# dianlutu.net
KiCad netlist of a schematic drawn in EAGLE
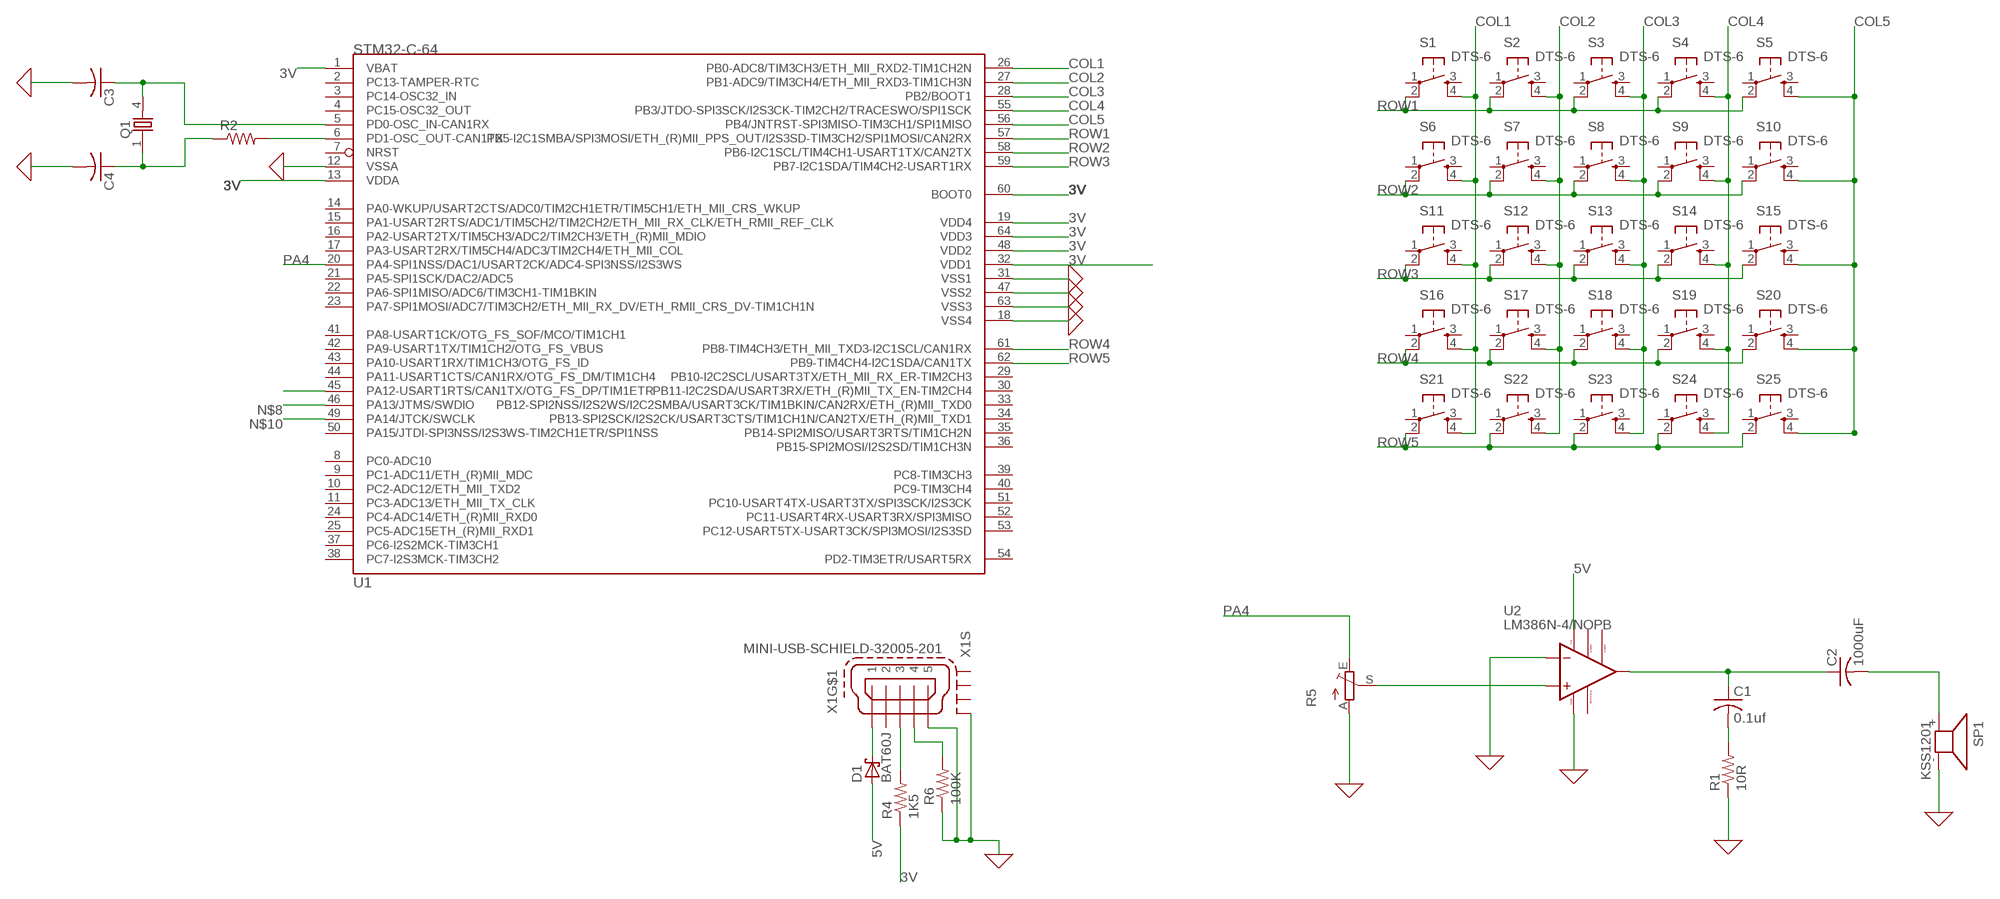
[diagram p0: schematic, sheet 1]

(export (version "E")
  (design (tool "Eeschema 10.0.6"))
  (components
    (comp (ref "C1")
      (value "0.1uf")
      (footprint "eagle-import:C0805")
      (libsource (lib "eagle-import") (part "C-USC0805"))
    )
    (comp (ref "C2")
      (value "1000uF")
      (footprint "eagle-import:C0805")
      (libsource (lib "eagle-import") (part "C-USC0805"))
    )
    (comp (ref "C3")
      (value "C-USC0805")
      (footprint "eagle-import:C0805")
      (libsource (lib "eagle-import") (part "C-USC0805"))
    )
    (comp (ref "C4")
      (value "C-USC0805")
      (footprint "eagle-import:C0805")
      (libsource (lib "eagle-import") (part "C-USC0805"))
    )
    (comp (ref "D1")
      (value "BAT60J")
      (footprint "eagle-import:SOD323_ST")
      (libsource (lib "eagle-import") (part "BAT60J"))
    )
    (comp (ref "Q1")
      (value "86SMX")
      (footprint "eagle-import:86SMX")
      (fields (field (name "MF") "C-MAC  FREQUENCY PRODUCTS LTD") (field (name "MPN") "XTAL003321- 86SMX"))
      (libsource (lib "eagle-import") (part "86SMX"))
    )
    (comp (ref "R1")
      (value "10R")
      (footprint "eagle-import:R0805")
      (libsource (lib "eagle-import") (part "R-US_R0805"))
    )
    (comp (ref "R2")
      (value "R-US_R0805")
      (footprint "eagle-import:R0805")
      (libsource (lib "eagle-import") (part "R-US_R0805"))
    )
    (comp (ref "R4")
      (value "1K5")
      (footprint "eagle-import:R0805")
      (libsource (lib "eagle-import") (part "resistor_348_R-US_R0805"))
    )
    (comp (ref "R5")
      (value "TRIM_EU-S63S")
      (footprint "eagle-import:S63S")
      (libsource (lib "eagle-import") (part "TRIM_EU-S63S"))
    )
    (comp (ref "R6")
      (value "100K")
      (footprint "eagle-import:M0805")
      (libsource (lib "eagle-import") (part "resistor_348_R-US_M0805"))
    )
    (comp (ref "S1")
      (value "DTS-6")
      (footprint "eagle-import:DTS-6")
      (libsource (lib "eagle-import") (part "DTS-6"))
    )
    (comp (ref "S2")
      (value "DTS-6")
      (footprint "eagle-import:DTS-6")
      (libsource (lib "eagle-import") (part "DTS-6"))
    )
    (comp (ref "S3")
      (value "DTS-6")
      (footprint "eagle-import:DTS-6")
      (libsource (lib "eagle-import") (part "DTS-6"))
    )
    (comp (ref "S4")
      (value "DTS-6")
      (footprint "eagle-import:DTS-6")
      (libsource (lib "eagle-import") (part "DTS-6"))
    )
    (comp (ref "S5")
      (value "DTS-6")
      (footprint "eagle-import:DTS-6")
      (libsource (lib "eagle-import") (part "DTS-6"))
    )
    (comp (ref "S6")
      (value "DTS-6")
      (footprint "eagle-import:DTS-6")
      (libsource (lib "eagle-import") (part "DTS-6"))
    )
    (comp (ref "S7")
      (value "DTS-6")
      (footprint "eagle-import:DTS-6")
      (libsource (lib "eagle-import") (part "DTS-6"))
    )
    (comp (ref "S8")
      (value "DTS-6")
      (footprint "eagle-import:DTS-6")
      (libsource (lib "eagle-import") (part "DTS-6"))
    )
    (comp (ref "S9")
      (value "DTS-6")
      (footprint "eagle-import:DTS-6")
      (libsource (lib "eagle-import") (part "DTS-6"))
    )
    (comp (ref "S10")
      (value "DTS-6")
      (footprint "eagle-import:DTS-6")
      (libsource (lib "eagle-import") (part "DTS-6"))
    )
    (comp (ref "S11")
      (value "DTS-6")
      (footprint "eagle-import:DTS-6")
      (libsource (lib "eagle-import") (part "DTS-6"))
    )
    (comp (ref "S12")
      (value "DTS-6")
      (footprint "eagle-import:DTS-6")
      (libsource (lib "eagle-import") (part "DTS-6"))
    )
    (comp (ref "S13")
      (value "DTS-6")
      (footprint "eagle-import:DTS-6")
      (libsource (lib "eagle-import") (part "DTS-6"))
    )
    (comp (ref "S14")
      (value "DTS-6")
      (footprint "eagle-import:DTS-6")
      (libsource (lib "eagle-import") (part "DTS-6"))
    )
    (comp (ref "S15")
      (value "DTS-6")
      (footprint "eagle-import:DTS-6")
      (libsource (lib "eagle-import") (part "DTS-6"))
    )
    (comp (ref "S16")
      (value "DTS-6")
      (footprint "eagle-import:DTS-6")
      (libsource (lib "eagle-import") (part "DTS-6"))
    )
    (comp (ref "S17")
      (value "DTS-6")
      (footprint "eagle-import:DTS-6")
      (libsource (lib "eagle-import") (part "DTS-6"))
    )
    (comp (ref "S18")
      (value "DTS-6")
      (footprint "eagle-import:DTS-6")
      (libsource (lib "eagle-import") (part "DTS-6"))
    )
    (comp (ref "S19")
      (value "DTS-6")
      (footprint "eagle-import:DTS-6")
      (libsource (lib "eagle-import") (part "DTS-6"))
    )
    (comp (ref "S20")
      (value "DTS-6")
      (footprint "eagle-import:DTS-6")
      (libsource (lib "eagle-import") (part "DTS-6"))
    )
    (comp (ref "S21")
      (value "DTS-6")
      (footprint "eagle-import:DTS-6")
      (libsource (lib "eagle-import") (part "DTS-6"))
    )
    (comp (ref "S22")
      (value "DTS-6")
      (footprint "eagle-import:DTS-6")
      (libsource (lib "eagle-import") (part "DTS-6"))
    )
    (comp (ref "S23")
      (value "DTS-6")
      (footprint "eagle-import:DTS-6")
      (libsource (lib "eagle-import") (part "DTS-6"))
    )
    (comp (ref "S24")
      (value "DTS-6")
      (footprint "eagle-import:DTS-6")
      (libsource (lib "eagle-import") (part "DTS-6"))
    )
    (comp (ref "S25")
      (value "DTS-6")
      (footprint "eagle-import:DTS-6")
      (libsource (lib "eagle-import") (part "DTS-6"))
    )
    (comp (ref "SP1")
      (value "KSS1201")
      (footprint "eagle-import:KSS1201")
      (libsource (lib "eagle-import") (part "KSS1201"))
    )
    (comp (ref "U1")
      (value "STM32-C-64")
      (footprint "eagle-import:LQFP64")
      (libsource (lib "eagle-import") (part "STM32-C-64"))
    )
    (comp (ref "U2")
      (value "LM386N-4/NOPB")
      (footprint "eagle-import:DIP794W45P254L1016H508Q8")
      (fields (field (name "MF") "Texas Instruments"))
      (libsource (lib "eagle-import") (part "LM386N-4/NOPB"))
    )
    (comp (ref "X1")
      (value "MINI-USB-SCHIELD-32005-201")
      (footprint "eagle-import:32005-201")
      (libsource (lib "eagle-import") (part "MINI-USB-SCHIELD-32005-201"))
    )
  )
  (nets
    (net (code "1") (name "/3V") (class "Default")
      (node (ref "R4") (pin "1") (pinfunction "1_1") (pintype "passive"))
      (node (ref "U1") (pin "1") (pinfunction "VBAT_1") (pintype "power_in"))
      (node (ref "U1") (pin "13") (pinfunction "VDDA_13") (pintype "power_in"))
      (node (ref "U1") (pin "19") (pinfunction "VDD4_19") (pintype "bidirectional"))
      (node (ref "U1") (pin "32") (pinfunction "VDD1_32") (pintype "power_in"))
      (node (ref "U1") (pin "48") (pinfunction "VDD2_48") (pintype "power_in"))
      (node (ref "U1") (pin "60") (pinfunction "BOOT0_60") (pintype "input"))
      (node (ref "U1") (pin "64") (pinfunction "VDD3_64") (pintype "power_in"))
    )
    (net (code "2") (name "/5V") (class "Default")
      (node (ref "D1") (pin "A") (pinfunction "A_A") (pintype "passive"))
      (node (ref "U2") (pin "6") (pinfunction "VS_6") (pintype "power_in"))
    )
    (net (code "3") (name "/COL1") (class "Default")
      (node (ref "S1") (pin "4") (pinfunction "4_4") (pintype "passive"))
      (node (ref "S11") (pin "4") (pinfunction "4_4") (pintype "passive"))
      (node (ref "S16") (pin "4") (pinfunction "4_4") (pintype "passive"))
      (node (ref "S21") (pin "4") (pinfunction "4_4") (pintype "passive"))
      (node (ref "S6") (pin "4") (pinfunction "4_4") (pintype "passive"))
      (node (ref "U1") (pin "26") (pinfunction "PB0-ADC8/TIM3CH3/ETH_MII_RXD2-TIM1CH2N_26") (pintype "bidirectional"))
    )
    (net (code "4") (name "/COL2") (class "Default")
      (node (ref "S12") (pin "4") (pinfunction "4_4") (pintype "passive"))
      (node (ref "S17") (pin "4") (pinfunction "4_4") (pintype "passive"))
      (node (ref "S2") (pin "4") (pinfunction "4_4") (pintype "passive"))
      (node (ref "S22") (pin "4") (pinfunction "4_4") (pintype "passive"))
      (node (ref "S7") (pin "4") (pinfunction "4_4") (pintype "passive"))
      (node (ref "U1") (pin "27") (pinfunction "PB1-ADC9/TIM3CH4/ETH_MII_RXD3-TIM1CH3N_27") (pintype "bidirectional"))
    )
    (net (code "5") (name "/COL3") (class "Default")
      (node (ref "S13") (pin "4") (pinfunction "4_4") (pintype "passive"))
      (node (ref "S18") (pin "4") (pinfunction "4_4") (pintype "passive"))
      (node (ref "S23") (pin "4") (pinfunction "4_4") (pintype "passive"))
      (node (ref "S3") (pin "4") (pinfunction "4_4") (pintype "passive"))
      (node (ref "S8") (pin "4") (pinfunction "4_4") (pintype "passive"))
      (node (ref "U1") (pin "28") (pinfunction "PB2/BOOT1_28") (pintype "bidirectional"))
    )
    (net (code "6") (name "/COL4") (class "Default")
      (node (ref "S14") (pin "4") (pinfunction "4_4") (pintype "passive"))
      (node (ref "S19") (pin "4") (pinfunction "4_4") (pintype "passive"))
      (node (ref "S24") (pin "4") (pinfunction "4_4") (pintype "passive"))
      (node (ref "S4") (pin "4") (pinfunction "4_4") (pintype "passive"))
      (node (ref "S9") (pin "4") (pinfunction "4_4") (pintype "passive"))
      (node (ref "U1") (pin "55") (pinfunction "PB3/JTDO-SPI3SCK/I2S3CK-TIM2CH2/TRACESWO/SPI1SCK_55") (pintype "bidirectional"))
    )
    (net (code "7") (name "/COL5") (class "Default")
      (node (ref "S10") (pin "4") (pinfunction "4_4") (pintype "passive"))
      (node (ref "S15") (pin "4") (pinfunction "4_4") (pintype "passive"))
      (node (ref "S20") (pin "4") (pinfunction "4_4") (pintype "passive"))
      (node (ref "S25") (pin "4") (pinfunction "4_4") (pintype "passive"))
      (node (ref "S5") (pin "4") (pinfunction "4_4") (pintype "passive"))
      (node (ref "U1") (pin "56") (pinfunction "PB4/JNTRST-SPI3MISO-TIM3CH1/SPI1MISO_56") (pintype "bidirectional"))
    )
    (net (code "8") (name "/N$8") (class "Default")
      (node (ref "U1") (pin "46") (pinfunction "PA13/JTMS/SWDIO_46") (pintype "bidirectional"))
    )
    (net (code "9") (name "/N$10") (class "Default")
      (node (ref "U1") (pin "49") (pinfunction "PA14/JTCK/SWCLK_49") (pintype "bidirectional"))
    )
    (net (code "10") (name "/PA4") (class "Default")
      (node (ref "R5") (pin "E") (pinfunction "E_E") (pintype "passive"))
      (node (ref "U1") (pin "20") (pinfunction "PA4-SPI1NSS/DAC1/USART2CK/ADC4-SPI3NSS/I2S3WS_20") (pintype "bidirectional"))
    )
    (net (code "11") (name "/ROW1") (class "Default")
      (node (ref "S1") (pin "2") (pinfunction "2_2") (pintype "passive"))
      (node (ref "S2") (pin "2") (pinfunction "2_2") (pintype "passive"))
      (node (ref "S3") (pin "2") (pinfunction "2_2") (pintype "passive"))
      (node (ref "S4") (pin "2") (pinfunction "2_2") (pintype "passive"))
      (node (ref "S5") (pin "2") (pinfunction "2_2") (pintype "passive"))
      (node (ref "U1") (pin "57") (pinfunction "PB5-I2C1SMBA/SPI3MOSI/ETH_(R)MII_PPS_OUT/I2S3SD-TIM3CH2/SPI1MOSI/CAN2RX_57") (pintype "bidirectional"))
    )
    (net (code "12") (name "/ROW2") (class "Default")
      (node (ref "S10") (pin "2") (pinfunction "2_2") (pintype "passive"))
      (node (ref "S6") (pin "2") (pinfunction "2_2") (pintype "passive"))
      (node (ref "S7") (pin "2") (pinfunction "2_2") (pintype "passive"))
      (node (ref "S8") (pin "2") (pinfunction "2_2") (pintype "passive"))
      (node (ref "S9") (pin "2") (pinfunction "2_2") (pintype "passive"))
      (node (ref "U1") (pin "58") (pinfunction "PB6-I2C1SCL/TIM4CH1-USART1TX/CAN2TX_58") (pintype "bidirectional"))
    )
    (net (code "13") (name "/ROW3") (class "Default")
      (node (ref "S11") (pin "2") (pinfunction "2_2") (pintype "passive"))
      (node (ref "S12") (pin "2") (pinfunction "2_2") (pintype "passive"))
      (node (ref "S13") (pin "2") (pinfunction "2_2") (pintype "passive"))
      (node (ref "S14") (pin "2") (pinfunction "2_2") (pintype "passive"))
      (node (ref "S15") (pin "2") (pinfunction "2_2") (pintype "passive"))
      (node (ref "U1") (pin "59") (pinfunction "PB7-I2C1SDA/TIM4CH2-USART1RX_59") (pintype "bidirectional"))
    )
    (net (code "14") (name "/ROW4") (class "Default")
      (node (ref "S16") (pin "2") (pinfunction "2_2") (pintype "passive"))
      (node (ref "S17") (pin "2") (pinfunction "2_2") (pintype "passive"))
      (node (ref "S18") (pin "2") (pinfunction "2_2") (pintype "passive"))
      (node (ref "S19") (pin "2") (pinfunction "2_2") (pintype "passive"))
      (node (ref "S20") (pin "2") (pinfunction "2_2") (pintype "passive"))
      (node (ref "U1") (pin "61") (pinfunction "PB8-TIM4CH3/ETH_MII_TXD3-I2C1SCL/CAN1RX_61") (pintype "bidirectional"))
    )
    (net (code "15") (name "/ROW5") (class "Default")
      (node (ref "S21") (pin "2") (pinfunction "2_2") (pintype "passive"))
      (node (ref "S22") (pin "2") (pinfunction "2_2") (pintype "passive"))
      (node (ref "S23") (pin "2") (pinfunction "2_2") (pintype "passive"))
      (node (ref "S24") (pin "2") (pinfunction "2_2") (pintype "passive"))
      (node (ref "S25") (pin "2") (pinfunction "2_2") (pintype "passive"))
      (node (ref "U1") (pin "62") (pinfunction "PB9-TIM4CH4-I2C1SDA/CAN1TX_62") (pintype "bidirectional"))
    )
    (net (code "16") (name "GND") (class "Default")
      (node (ref "C3") (pin "2") (pinfunction "2_2") (pintype "passive"))
      (node (ref "C4") (pin "2") (pinfunction "2_2") (pintype "passive"))
      (node (ref "R1") (pin "1") (pinfunction "1_1") (pintype "passive"))
      (node (ref "R5") (pin "A") (pinfunction "A_A") (pintype "passive"))
      (node (ref "R6") (pin "1") (pinfunction "1_1") (pintype "passive"))
      (node (ref "SP1") (pin "-") (pinfunction "2_-") (pintype "passive"))
      (node (ref "U1") (pin "12") (pinfunction "VSSA_12") (pintype "power_in"))
      (node (ref "U1") (pin "18") (pinfunction "VSS4_18") (pintype "bidirectional"))
      (node (ref "U1") (pin "31") (pinfunction "VSS1_31") (pintype "power_in"))
      (node (ref "U1") (pin "47") (pinfunction "VSS2_47") (pintype "power_in"))
      (node (ref "U1") (pin "63") (pinfunction "VSS3_63") (pintype "power_in"))
      (node (ref "U2") (pin "2") (pinfunction "-INPUT_2") (pintype "input"))
      (node (ref "U2") (pin "4") (pinfunction "GND_4") (pintype "power_in"))
      (node (ref "X1") (pin "5") (pinfunction "5_5") (pintype "passive"))
      (node (ref "X1") (pin "M1") (pinfunction "S1_M1") (pintype "passive"))
    )
    (net (code "17") (name "Net-(C1-Pad2)") (class "Default")
      (node (ref "C1") (pin "2") (pinfunction "2_2") (pintype "passive"))
      (node (ref "R1") (pin "2") (pinfunction "2_2") (pintype "passive"))
    )
    (net (code "18") (name "Net-(C4-Pad1)") (class "Default")
      (node (ref "C4") (pin "1") (pinfunction "1_1") (pintype "passive"))
      (node (ref "Q1") (pin "1") (pinfunction "1_1") (pintype "passive"))
      (node (ref "R2") (pin "1") (pinfunction "1_1") (pintype "passive"))
    )
    (net (code "19") (name "Net-(D1-PadC)") (class "Default")
      (node (ref "D1") (pin "C") (pinfunction "C_C") (pintype "passive"))
      (node (ref "X1") (pin "1") (pinfunction "1_1") (pintype "passive"))
    )
    (net (code "20") (name "Net-(Q1-2)") (class "Default")
      (node (ref "C3") (pin "1") (pinfunction "1_1") (pintype "passive"))
      (node (ref "Q1") (pin "4") (pinfunction "2_4") (pintype "passive"))
      (node (ref "U1") (pin "5") (pinfunction "PD0-OSC_IN-CAN1RX_5") (pintype "input"))
    )
    (net (code "21") (name "Net-(R4-Pad2)") (class "Default")
      (node (ref "R4") (pin "2") (pinfunction "2_2") (pintype "passive"))
      (node (ref "X1") (pin "3") (pinfunction "3_3") (pintype "passive"))
    )
    (net (code "22") (name "Net-(R6-Pad2)") (class "Default")
      (node (ref "R6") (pin "2") (pinfunction "2_2") (pintype "passive"))
      (node (ref "X1") (pin "4") (pinfunction "4_4") (pintype "passive"))
    )
    (net (code "23") (name "Net-(SP1-1)") (class "Default")
      (node (ref "C2") (pin "2") (pinfunction "2_2") (pintype "passive"))
      (node (ref "SP1") (pin "+") (pinfunction "1_+") (pintype "passive"))
    )
    (net (code "24") (name "Net-(U1-PD1-OSC_OUT-CAN1TX)") (class "Default")
      (node (ref "R2") (pin "2") (pinfunction "2_2") (pintype "passive"))
      (node (ref "U1") (pin "6") (pinfunction "PD1-OSC_OUT-CAN1TX_6") (pintype "output"))
    )
    (net (code "25") (name "Net-(U2-+INPUT)") (class "Default")
      (node (ref "R5") (pin "S") (pinfunction "S_S") (pintype "passive"))
      (node (ref "U2") (pin "3") (pinfunction "+INPUT_3") (pintype "input"))
    )
    (net (code "26") (name "Net-(U2-VOUT)") (class "Default")
      (node (ref "C1") (pin "1") (pinfunction "1_1") (pintype "passive"))
      (node (ref "C2") (pin "1") (pinfunction "1_1") (pintype "passive"))
      (node (ref "U2") (pin "5") (pinfunction "VOUT_5") (pintype "output"))
    )
    (net (code "27") (name "unconnected-(S1-Pad1)") (class "Default")
      (node (ref "S1") (pin "1") (pinfunction "1_1") (pintype "passive"))
    )
    (net (code "28") (name "unconnected-(S1-Pad3)") (class "Default")
      (node (ref "S1") (pin "3") (pinfunction "3_3") (pintype "passive"))
    )
    (net (code "29") (name "unconnected-(S2-Pad1)") (class "Default")
      (node (ref "S2") (pin "1") (pinfunction "1_1") (pintype "passive"))
    )
    (net (code "30") (name "unconnected-(S2-Pad3)") (class "Default")
      (node (ref "S2") (pin "3") (pinfunction "3_3") (pintype "passive"))
    )
    (net (code "31") (name "unconnected-(S3-Pad1)") (class "Default")
      (node (ref "S3") (pin "1") (pinfunction "1_1") (pintype "passive"))
    )
    (net (code "32") (name "unconnected-(S3-Pad3)") (class "Default")
      (node (ref "S3") (pin "3") (pinfunction "3_3") (pintype "passive"))
    )
    (net (code "33") (name "unconnected-(S4-Pad1)") (class "Default")
      (node (ref "S4") (pin "1") (pinfunction "1_1") (pintype "passive"))
    )
    (net (code "34") (name "unconnected-(S4-Pad3)") (class "Default")
      (node (ref "S4") (pin "3") (pinfunction "3_3") (pintype "passive"))
    )
    (net (code "35") (name "unconnected-(S5-Pad1)") (class "Default")
      (node (ref "S5") (pin "1") (pinfunction "1_1") (pintype "passive"))
    )
    (net (code "36") (name "unconnected-(S5-Pad3)") (class "Default")
      (node (ref "S5") (pin "3") (pinfunction "3_3") (pintype "passive"))
    )
    (net (code "37") (name "unconnected-(S6-Pad1)") (class "Default")
      (node (ref "S6") (pin "1") (pinfunction "1_1") (pintype "passive"))
    )
    (net (code "38") (name "unconnected-(S6-Pad3)") (class "Default")
      (node (ref "S6") (pin "3") (pinfunction "3_3") (pintype "passive"))
    )
    (net (code "39") (name "unconnected-(S7-Pad1)") (class "Default")
      (node (ref "S7") (pin "1") (pinfunction "1_1") (pintype "passive"))
    )
    (net (code "40") (name "unconnected-(S7-Pad3)") (class "Default")
      (node (ref "S7") (pin "3") (pinfunction "3_3") (pintype "passive"))
    )
    (net (code "41") (name "unconnected-(S8-Pad1)") (class "Default")
      (node (ref "S8") (pin "1") (pinfunction "1_1") (pintype "passive"))
    )
    (net (code "42") (name "unconnected-(S8-Pad3)") (class "Default")
      (node (ref "S8") (pin "3") (pinfunction "3_3") (pintype "passive"))
    )
    (net (code "43") (name "unconnected-(S9-Pad1)") (class "Default")
      (node (ref "S9") (pin "1") (pinfunction "1_1") (pintype "passive"))
    )
    (net (code "44") (name "unconnected-(S9-Pad3)") (class "Default")
      (node (ref "S9") (pin "3") (pinfunction "3_3") (pintype "passive"))
    )
    (net (code "45") (name "unconnected-(S10-Pad1)") (class "Default")
      (node (ref "S10") (pin "1") (pinfunction "1_1") (pintype "passive"))
    )
    (net (code "46") (name "unconnected-(S10-Pad3)") (class "Default")
      (node (ref "S10") (pin "3") (pinfunction "3_3") (pintype "passive"))
    )
    (net (code "47") (name "unconnected-(S11-Pad1)") (class "Default")
      (node (ref "S11") (pin "1") (pinfunction "1_1") (pintype "passive"))
    )
    (net (code "48") (name "unconnected-(S11-Pad3)") (class "Default")
      (node (ref "S11") (pin "3") (pinfunction "3_3") (pintype "passive"))
    )
    (net (code "49") (name "unconnected-(S12-Pad1)") (class "Default")
      (node (ref "S12") (pin "1") (pinfunction "1_1") (pintype "passive"))
    )
    (net (code "50") (name "unconnected-(S12-Pad3)") (class "Default")
      (node (ref "S12") (pin "3") (pinfunction "3_3") (pintype "passive"))
    )
    (net (code "51") (name "unconnected-(S13-Pad1)") (class "Default")
      (node (ref "S13") (pin "1") (pinfunction "1_1") (pintype "passive"))
    )
    (net (code "52") (name "unconnected-(S13-Pad3)") (class "Default")
      (node (ref "S13") (pin "3") (pinfunction "3_3") (pintype "passive"))
    )
    (net (code "53") (name "unconnected-(S14-Pad1)") (class "Default")
      (node (ref "S14") (pin "1") (pinfunction "1_1") (pintype "passive"))
    )
    (net (code "54") (name "unconnected-(S14-Pad3)") (class "Default")
      (node (ref "S14") (pin "3") (pinfunction "3_3") (pintype "passive"))
    )
    (net (code "55") (name "unconnected-(S15-Pad1)") (class "Default")
      (node (ref "S15") (pin "1") (pinfunction "1_1") (pintype "passive"))
    )
    (net (code "56") (name "unconnected-(S15-Pad3)") (class "Default")
      (node (ref "S15") (pin "3") (pinfunction "3_3") (pintype "passive"))
    )
    (net (code "57") (name "unconnected-(S16-Pad1)") (class "Default")
      (node (ref "S16") (pin "1") (pinfunction "1_1") (pintype "passive"))
    )
    (net (code "58") (name "unconnected-(S16-Pad3)") (class "Default")
      (node (ref "S16") (pin "3") (pinfunction "3_3") (pintype "passive"))
    )
    (net (code "59") (name "unconnected-(S17-Pad1)") (class "Default")
      (node (ref "S17") (pin "1") (pinfunction "1_1") (pintype "passive"))
    )
    (net (code "60") (name "unconnected-(S17-Pad3)") (class "Default")
      (node (ref "S17") (pin "3") (pinfunction "3_3") (pintype "passive"))
    )
    (net (code "61") (name "unconnected-(S18-Pad1)") (class "Default")
      (node (ref "S18") (pin "1") (pinfunction "1_1") (pintype "passive"))
    )
    (net (code "62") (name "unconnected-(S18-Pad3)") (class "Default")
      (node (ref "S18") (pin "3") (pinfunction "3_3") (pintype "passive"))
    )
    (net (code "63") (name "unconnected-(S19-Pad1)") (class "Default")
      (node (ref "S19") (pin "1") (pinfunction "1_1") (pintype "passive"))
    )
    (net (code "64") (name "unconnected-(S19-Pad3)") (class "Default")
      (node (ref "S19") (pin "3") (pinfunction "3_3") (pintype "passive"))
    )
    (net (code "65") (name "unconnected-(S20-Pad1)") (class "Default")
      (node (ref "S20") (pin "1") (pinfunction "1_1") (pintype "passive"))
    )
    (net (code "66") (name "unconnected-(S20-Pad3)") (class "Default")
      (node (ref "S20") (pin "3") (pinfunction "3_3") (pintype "passive"))
    )
    (net (code "67") (name "unconnected-(S21-Pad1)") (class "Default")
      (node (ref "S21") (pin "1") (pinfunction "1_1") (pintype "passive"))
    )
    (net (code "68") (name "unconnected-(S21-Pad3)") (class "Default")
      (node (ref "S21") (pin "3") (pinfunction "3_3") (pintype "passive"))
    )
    (net (code "69") (name "unconnected-(S22-Pad1)") (class "Default")
      (node (ref "S22") (pin "1") (pinfunction "1_1") (pintype "passive"))
    )
    (net (code "70") (name "unconnected-(S22-Pad3)") (class "Default")
      (node (ref "S22") (pin "3") (pinfunction "3_3") (pintype "passive"))
    )
    (net (code "71") (name "unconnected-(S23-Pad1)") (class "Default")
      (node (ref "S23") (pin "1") (pinfunction "1_1") (pintype "passive"))
    )
    (net (code "72") (name "unconnected-(S23-Pad3)") (class "Default")
      (node (ref "S23") (pin "3") (pinfunction "3_3") (pintype "passive"))
    )
    (net (code "73") (name "unconnected-(S24-Pad1)") (class "Default")
      (node (ref "S24") (pin "1") (pinfunction "1_1") (pintype "passive"))
    )
    (net (code "74") (name "unconnected-(S24-Pad3)") (class "Default")
      (node (ref "S24") (pin "3") (pinfunction "3_3") (pintype "passive"))
    )
    (net (code "75") (name "unconnected-(S25-Pad1)") (class "Default")
      (node (ref "S25") (pin "1") (pinfunction "1_1") (pintype "passive"))
    )
    (net (code "76") (name "unconnected-(S25-Pad3)") (class "Default")
      (node (ref "S25") (pin "3") (pinfunction "3_3") (pintype "passive"))
    )
    (net (code "77") (name "unconnected-(U1-NRST-Pad7)") (class "Default")
      (node (ref "U1") (pin "7") (pinfunction "NRST_7") (pintype "bidirectional"))
    )
    (net (code "78") (name "unconnected-(U1-PA0-WKUP{slash}USART2CTS{slash}ADC0{slash}TIM2CH1ETR{slash}TIM5CH1{slash}ETH_MII_CRS_WKUP-Pad14)") (class "Default")
      (node (ref "U1") (pin "14") (pinfunction "PA0-WKUP/USART2CTS/ADC0/TIM2CH1ETR/TIM5CH1/ETH_MII_CRS_WKUP_14") (pintype "bidirectional"))
    )
    (net (code "79") (name "unconnected-(U1-PA1-USART2RTS{slash}ADC1{slash}TIM5CH2{slash}TIM2CH2{slash}ETH_MII_RX_CLK{slash}ETH_RMII_REF_CLK-Pad15)") (class "Default")
      (node (ref "U1") (pin "15") (pinfunction "PA1-USART2RTS/ADC1/TIM5CH2/TIM2CH2/ETH_MII_RX_CLK/ETH_RMII_REF_CLK_15") (pintype "bidirectional"))
    )
    (net (code "80") (name "unconnected-(U1-PA2-USART2TX{slash}TIM5CH3{slash}ADC2{slash}TIM2CH3{slash}ETH_(R)MII_MDIO-Pad16)") (class "Default")
      (node (ref "U1") (pin "16") (pinfunction "PA2-USART2TX/TIM5CH3/ADC2/TIM2CH3/ETH_(R)MII_MDIO_16") (pintype "bidirectional"))
    )
    (net (code "81") (name "unconnected-(U1-PA3-USART2RX{slash}TIM5CH4{slash}ADC3{slash}TIM2CH4{slash}ETH_MII_COL-Pad17)") (class "Default")
      (node (ref "U1") (pin "17") (pinfunction "PA3-USART2RX/TIM5CH4/ADC3/TIM2CH4/ETH_MII_COL_17") (pintype "bidirectional"))
    )
    (net (code "82") (name "unconnected-(U1-PA5-SPI1SCK{slash}DAC2{slash}ADC5-Pad21)") (class "Default")
      (node (ref "U1") (pin "21") (pinfunction "PA5-SPI1SCK/DAC2/ADC5_21") (pintype "bidirectional"))
    )
    (net (code "83") (name "unconnected-(U1-PA6-SPI1MISO{slash}ADC6{slash}TIM3CH1-TIM1BKIN-Pad22)") (class "Default")
      (node (ref "U1") (pin "22") (pinfunction "PA6-SPI1MISO/ADC6/TIM3CH1-TIM1BKIN_22") (pintype "bidirectional"))
    )
    (net (code "84") (name "unconnected-(U1-PA7-SPI1MOSI{slash}ADC7{slash}TIM3CH2{slash}ETH_MII_RX_DV{slash}ETH_RMII_CRS_DV-TIM1CH1N-Pad23)") (class "Default")
      (node (ref "U1") (pin "23") (pinfunction "PA7-SPI1MOSI/ADC7/TIM3CH2/ETH_MII_RX_DV/ETH_RMII_CRS_DV-TIM1CH1N_23") (pintype "bidirectional"))
    )
    (net (code "85") (name "unconnected-(U1-PA8-USART1CK{slash}OTG_FS_SOF{slash}MCO{slash}TIM1CH1-Pad41)") (class "Default")
      (node (ref "U1") (pin "41") (pinfunction "PA8-USART1CK/OTG_FS_SOF/MCO/TIM1CH1_41") (pintype "bidirectional"))
    )
    (net (code "86") (name "unconnected-(U1-PA9-USART1TX{slash}TIM1CH2{slash}OTG_FS_VBUS-Pad42)") (class "Default")
      (node (ref "U1") (pin "42") (pinfunction "PA9-USART1TX/TIM1CH2/OTG_FS_VBUS_42") (pintype "bidirectional"))
    )
    (net (code "87") (name "unconnected-(U1-PA10-USART1RX{slash}TIM1CH3{slash}OTG_FS_ID-Pad43)") (class "Default")
      (node (ref "U1") (pin "43") (pinfunction "PA10-USART1RX/TIM1CH3/OTG_FS_ID_43") (pintype "bidirectional"))
    )
    (net (code "88") (name "unconnected-(U1-PA11-USART1CTS{slash}CAN1RX{slash}OTG_FS_DM{slash}TIM1CH4-Pad44)") (class "Default")
      (node (ref "U1") (pin "44") (pinfunction "PA11-USART1CTS/CAN1RX/OTG_FS_DM/TIM1CH4_44") (pintype "bidirectional"))
    )
    (net (code "89") (name "unconnected-(U1-PA12-USART1RTS{slash}CAN1TX{slash}OTG_FS_DP{slash}TIM1ETR-Pad45)") (class "Default")
      (node (ref "U1") (pin "45") (pinfunction "PA12-USART1RTS/CAN1TX/OTG_FS_DP/TIM1ETR_45") (pintype "bidirectional"))
    )
    (net (code "90") (name "unconnected-(U1-PA15{slash}JTDI-SPI3NSS{slash}I2S3WS-TIM2CH1ETR{slash}SPI1NSS-Pad50)") (class "Default")
      (node (ref "U1") (pin "50") (pinfunction "PA15/JTDI-SPI3NSS/I2S3WS-TIM2CH1ETR/SPI1NSS_50") (pintype "bidirectional"))
    )
    (net (code "91") (name "unconnected-(U1-PB10-I2C2SCL{slash}USART3TX{slash}ETH_MII_RX_ER-TIM2CH3-Pad29)") (class "Default")
      (node (ref "U1") (pin "29") (pinfunction "PB10-I2C2SCL/USART3TX/ETH_MII_RX_ER-TIM2CH3_29") (pintype "bidirectional"))
    )
    (net (code "92") (name "unconnected-(U1-PB11-I2C2SDA{slash}USART3RX{slash}ETH_(R)MII_TX_EN-TIM2CH4-Pad30)") (class "Default")
      (node (ref "U1") (pin "30") (pinfunction "PB11-I2C2SDA/USART3RX/ETH_(R)MII_TX_EN-TIM2CH4_30") (pintype "bidirectional"))
    )
    (net (code "93") (name "unconnected-(U1-PB12-SPI2NSS{slash}I2S2WS{slash}I2C2SMBA{slash}USART3CK{slash}TIM1BKIN{slash}CAN2RX{slash}ETH_(R)MII_TXD0-Pad33)") (class "Default")
      (node (ref "U1") (pin "33") (pinfunction "PB12-SPI2NSS/I2S2WS/I2C2SMBA/USART3CK/TIM1BKIN/CAN2RX/ETH_(R)MII_TXD0_33") (pintype "bidirectional"))
    )
    (net (code "94") (name "unconnected-(U1-PB13-SPI2SCK{slash}I2S2CK{slash}USART3CTS{slash}TIM1CH1N{slash}CAN2TX{slash}ETH_(R)MII_TXD1-Pad34)") (class "Default")
      (node (ref "U1") (pin "34") (pinfunction "PB13-SPI2SCK/I2S2CK/USART3CTS/TIM1CH1N/CAN2TX/ETH_(R)MII_TXD1_34") (pintype "bidirectional"))
    )
    (net (code "95") (name "unconnected-(U1-PB14-SPI2MISO{slash}USART3RTS{slash}TIM1CH2N-Pad35)") (class "Default")
      (node (ref "U1") (pin "35") (pinfunction "PB14-SPI2MISO/USART3RTS/TIM1CH2N_35") (pintype "bidirectional"))
    )
    (net (code "96") (name "unconnected-(U1-PB15-SPI2MOSI{slash}I2S2SD{slash}TIM1CH3N-Pad36)") (class "Default")
      (node (ref "U1") (pin "36") (pinfunction "PB15-SPI2MOSI/I2S2SD/TIM1CH3N_36") (pintype "bidirectional"))
    )
    (net (code "97") (name "unconnected-(U1-PC0-ADC10-Pad8)") (class "Default")
      (node (ref "U1") (pin "8") (pinfunction "PC0-ADC10_8") (pintype "bidirectional"))
    )
    (net (code "98") (name "unconnected-(U1-PC1-ADC11{slash}ETH_(R)MII_MDC-Pad9)") (class "Default")
      (node (ref "U1") (pin "9") (pinfunction "PC1-ADC11/ETH_(R)MII_MDC_9") (pintype "bidirectional"))
    )
    (net (code "99") (name "unconnected-(U1-PC2-ADC12{slash}ETH_MII_TXD2-Pad10)") (class "Default")
      (node (ref "U1") (pin "10") (pinfunction "PC2-ADC12/ETH_MII_TXD2_10") (pintype "bidirectional"))
    )
    (net (code "100") (name "unconnected-(U1-PC3-ADC13{slash}ETH_MII_TX_CLK-Pad11)") (class "Default")
      (node (ref "U1") (pin "11") (pinfunction "PC3-ADC13/ETH_MII_TX_CLK_11") (pintype "bidirectional"))
    )
    (net (code "101") (name "unconnected-(U1-PC4-ADC14{slash}ETH_(R)MII_RXD0-Pad24)") (class "Default")
      (node (ref "U1") (pin "24") (pinfunction "PC4-ADC14/ETH_(R)MII_RXD0_24") (pintype "bidirectional"))
    )
    (net (code "102") (name "unconnected-(U1-PC5-ADC15ETH_(R)MII_RXD1-Pad25)") (class "Default")
      (node (ref "U1") (pin "25") (pinfunction "PC5-ADC15ETH_(R)MII_RXD1_25") (pintype "bidirectional"))
    )
    (net (code "103") (name "unconnected-(U1-PC6-I2S2MCK-TIM3CH1-Pad37)") (class "Default")
      (node (ref "U1") (pin "37") (pinfunction "PC6-I2S2MCK-TIM3CH1_37") (pintype "bidirectional"))
    )
    (net (code "104") (name "unconnected-(U1-PC7-I2S3MCK-TIM3CH2-Pad38)") (class "Default")
      (node (ref "U1") (pin "38") (pinfunction "PC7-I2S3MCK-TIM3CH2_38") (pintype "bidirectional"))
    )
    (net (code "105") (name "unconnected-(U1-PC8-TIM3CH3-Pad39)") (class "Default")
      (node (ref "U1") (pin "39") (pinfunction "PC8-TIM3CH3_39") (pintype "bidirectional"))
    )
    (net (code "106") (name "unconnected-(U1-PC9-TIM3CH4-Pad40)") (class "Default")
      (node (ref "U1") (pin "40") (pinfunction "PC9-TIM3CH4_40") (pintype "bidirectional"))
    )
    (net (code "107") (name "unconnected-(U1-PC10-USART4TX-USART3TX{slash}SPI3SCK{slash}I2S3CK-Pad51)") (class "Default")
      (node (ref "U1") (pin "51") (pinfunction "PC10-USART4TX-USART3TX/SPI3SCK/I2S3CK_51") (pintype "bidirectional"))
    )
    (net (code "108") (name "unconnected-(U1-PC11-USART4RX-USART3RX{slash}SPI3MISO-Pad52)") (class "Default")
      (node (ref "U1") (pin "52") (pinfunction "PC11-USART4RX-USART3RX/SPI3MISO_52") (pintype "bidirectional"))
    )
    (net (code "109") (name "unconnected-(U1-PC12-USART5TX-USART3CK{slash}SPI3MOSI{slash}I2S3SD-Pad53)") (class "Default")
      (node (ref "U1") (pin "53") (pinfunction "PC12-USART5TX-USART3CK/SPI3MOSI/I2S3SD_53") (pintype "bidirectional"))
    )
    (net (code "110") (name "unconnected-(U1-PC13-TAMPER-RTC-Pad2)") (class "Default")
      (node (ref "U1") (pin "2") (pinfunction "PC13-TAMPER-RTC_2") (pintype "bidirectional"))
    )
    (net (code "111") (name "unconnected-(U1-PC14-OSC32_IN-Pad3)") (class "Default")
      (node (ref "U1") (pin "3") (pinfunction "PC14-OSC32_IN_3") (pintype "bidirectional"))
    )
    (net (code "112") (name "unconnected-(U1-PC15-OSC32_OUT-Pad4)") (class "Default")
      (node (ref "U1") (pin "4") (pinfunction "PC15-OSC32_OUT_4") (pintype "bidirectional"))
    )
    (net (code "113") (name "unconnected-(U1-PD2-TIM3ETR{slash}USART5RX-Pad54)") (class "Default")
      (node (ref "U1") (pin "54") (pinfunction "PD2-TIM3ETR/USART5RX_54") (pintype "bidirectional"))
    )
    (net (code "114") (name "unconnected-(U2-BYPASS-Pad7)") (class "Default")
      (node (ref "U2") (pin "7") (pinfunction "BYPASS_7") (pintype "output"))
    )
    (net (code "115") (name "unconnected-(U2-GAIN1-Pad1)") (class "Default")
      (node (ref "U2") (pin "1") (pinfunction "GAIN1_1") (pintype "passive"))
    )
    (net (code "116") (name "unconnected-(U2-GAIN2-Pad8)") (class "Default")
      (node (ref "U2") (pin "8") (pinfunction "GAIN2_8") (pintype "passive"))
    )
    (net (code "117") (name "unconnected-(X1-Pad2)") (class "Default")
      (node (ref "X1") (pin "2") (pinfunction "2_2") (pintype "passive"))
    )
    (net (code "118") (name "unconnected-(X1B-S2-PadM2)") (class "Default")
      (node (ref "X1") (pin "M2") (pinfunction "S2_M2") (pintype "passive"))
    )
    (net (code "119") (name "unconnected-(X1B-S3-PadM3)") (class "Default")
      (node (ref "X1") (pin "M3") (pinfunction "S3_M3") (pintype "passive"))
    )
    (net (code "120") (name "unconnected-(X1B-S4-PadM4)") (class "Default")
      (node (ref "X1") (pin "M4") (pinfunction "S4_M4") (pintype "passive"))
    )
  )
)
